# tact-switches2.net
KiCad netlist of a schematic drawn in EAGLE
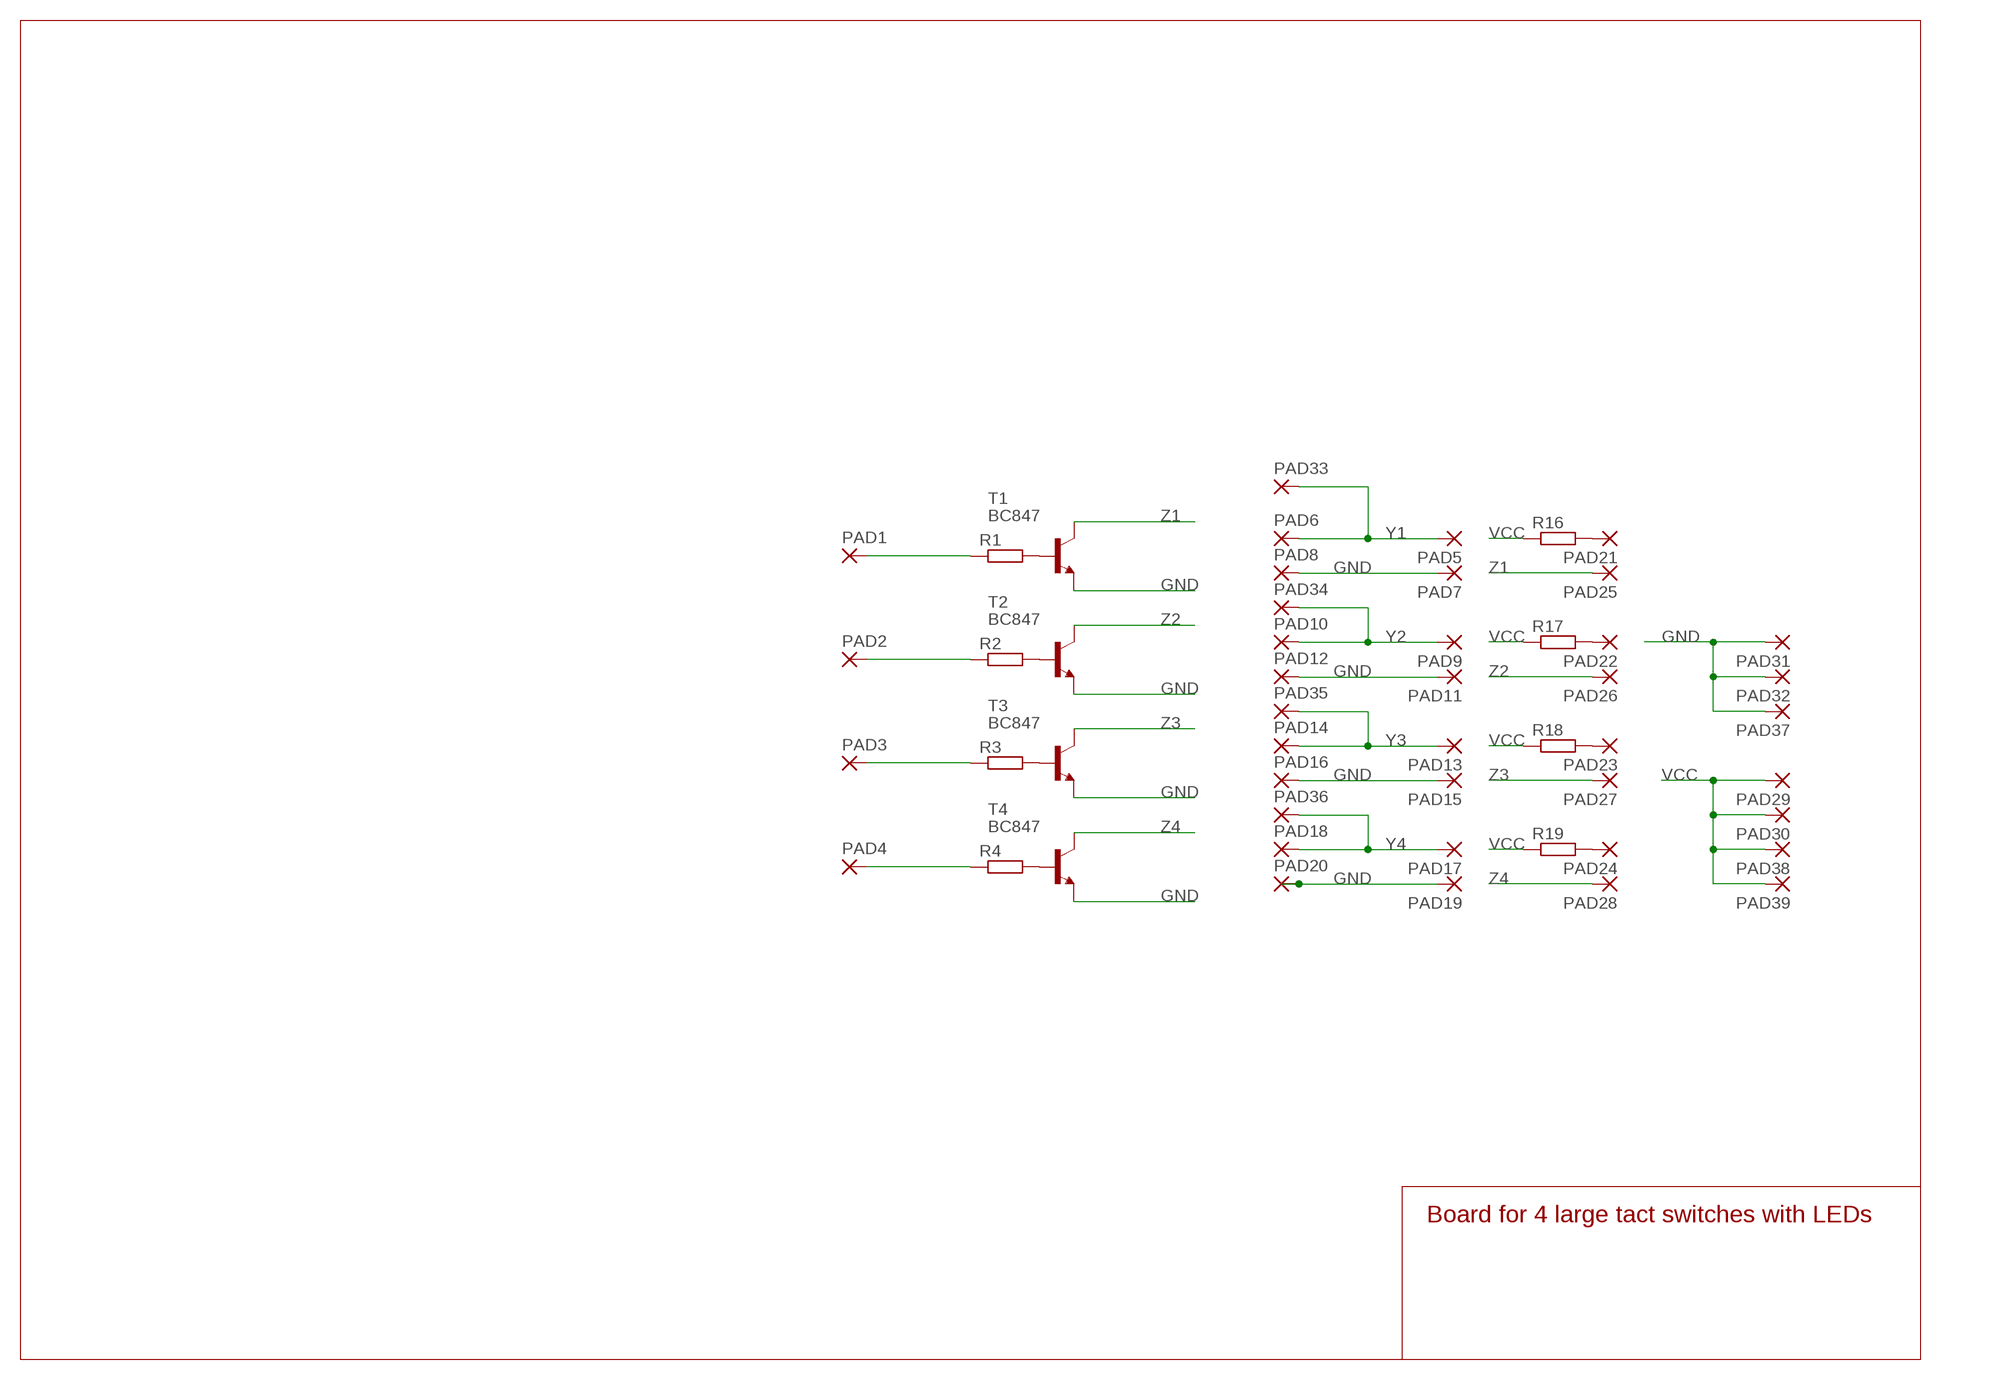
[diagram p0: schematic, sheet 1]

(export (version "E")
  (design (tool "Eeschema 10.0.6"))
  (components
    (comp (ref "PAD1")
      (value "1,6/0,8")
      (footprint "eagle-import:1,6_0,8")
      (libsource (lib "eagle-import") (part "1,6/0,8"))
    )
    (comp (ref "PAD2")
      (value "1,6/0,8")
      (footprint "eagle-import:1,6_0,8")
      (libsource (lib "eagle-import") (part "1,6/0,8"))
    )
    (comp (ref "PAD3")
      (value "1,6/0,8")
      (footprint "eagle-import:1,6_0,8")
      (libsource (lib "eagle-import") (part "1,6/0,8"))
    )
    (comp (ref "PAD4")
      (value "1,6/0,8")
      (footprint "eagle-import:1,6_0,8")
      (libsource (lib "eagle-import") (part "1,6/0,8"))
    )
    (comp (ref "PAD5")
      (value "1,6/0,8")
      (footprint "eagle-import:1,6_0,8")
      (libsource (lib "eagle-import") (part "1,6/0,8"))
    )
    (comp (ref "PAD6")
      (value "1,6/0,8")
      (footprint "eagle-import:1,6_0,8")
      (libsource (lib "eagle-import") (part "1,6/0,8"))
    )
    (comp (ref "PAD7")
      (value "1,6/0,8")
      (footprint "eagle-import:1,6_0,8")
      (libsource (lib "eagle-import") (part "1,6/0,8"))
    )
    (comp (ref "PAD8")
      (value "1,6/0,8")
      (footprint "eagle-import:1,6_0,8")
      (libsource (lib "eagle-import") (part "1,6/0,8"))
    )
    (comp (ref "PAD9")
      (value "1,6/0,8")
      (footprint "eagle-import:1,6_0,8")
      (libsource (lib "eagle-import") (part "1,6/0,8"))
    )
    (comp (ref "PAD10")
      (value "1,6/0,8")
      (footprint "eagle-import:1,6_0,8")
      (libsource (lib "eagle-import") (part "1,6/0,8"))
    )
    (comp (ref "PAD11")
      (value "1,6/0,8")
      (footprint "eagle-import:1,6_0,8")
      (libsource (lib "eagle-import") (part "1,6/0,8"))
    )
    (comp (ref "PAD12")
      (value "1,6/0,8")
      (footprint "eagle-import:1,6_0,8")
      (libsource (lib "eagle-import") (part "1,6/0,8"))
    )
    (comp (ref "PAD13")
      (value "1,6/0,8")
      (footprint "eagle-import:1,6_0,8")
      (libsource (lib "eagle-import") (part "1,6/0,8"))
    )
    (comp (ref "PAD14")
      (value "1,6/0,8")
      (footprint "eagle-import:1,6_0,8")
      (libsource (lib "eagle-import") (part "1,6/0,8"))
    )
    (comp (ref "PAD15")
      (value "1,6/0,8")
      (footprint "eagle-import:1,6_0,8")
      (libsource (lib "eagle-import") (part "1,6/0,8"))
    )
    (comp (ref "PAD16")
      (value "1,6/0,8")
      (footprint "eagle-import:1,6_0,8")
      (libsource (lib "eagle-import") (part "1,6/0,8"))
    )
    (comp (ref "PAD17")
      (value "1,6/0,8")
      (footprint "eagle-import:1,6_0,8")
      (libsource (lib "eagle-import") (part "1,6/0,8"))
    )
    (comp (ref "PAD18")
      (value "1,6/0,8")
      (footprint "eagle-import:1,6_0,8")
      (libsource (lib "eagle-import") (part "1,6/0,8"))
    )
    (comp (ref "PAD19")
      (value "1,6/0,8")
      (footprint "eagle-import:1,6_0,8")
      (libsource (lib "eagle-import") (part "1,6/0,8"))
    )
    (comp (ref "PAD20")
      (value "1,6/0,8")
      (footprint "eagle-import:1,6_0,8")
      (libsource (lib "eagle-import") (part "1,6/0,8"))
    )
    (comp (ref "PAD21")
      (value "1,6/0,8")
      (footprint "eagle-import:1,6_0,8")
      (libsource (lib "eagle-import") (part "1,6/0,8"))
    )
    (comp (ref "PAD22")
      (value "1,6/0,8")
      (footprint "eagle-import:1,6_0,8")
      (libsource (lib "eagle-import") (part "1,6/0,8"))
    )
    (comp (ref "PAD23")
      (value "1,6/0,8")
      (footprint "eagle-import:1,6_0,8")
      (libsource (lib "eagle-import") (part "1,6/0,8"))
    )
    (comp (ref "PAD24")
      (value "1,6/0,8")
      (footprint "eagle-import:1,6_0,8")
      (libsource (lib "eagle-import") (part "1,6/0,8"))
    )
    (comp (ref "PAD25")
      (value "1,6/0,8")
      (footprint "eagle-import:1,6_0,8")
      (libsource (lib "eagle-import") (part "1,6/0,8"))
    )
    (comp (ref "PAD26")
      (value "1,6/0,8")
      (footprint "eagle-import:1,6_0,8")
      (libsource (lib "eagle-import") (part "1,6/0,8"))
    )
    (comp (ref "PAD27")
      (value "1,6/0,8")
      (footprint "eagle-import:1,6_0,8")
      (libsource (lib "eagle-import") (part "1,6/0,8"))
    )
    (comp (ref "PAD28")
      (value "1,6/0,8")
      (footprint "eagle-import:1,6_0,8")
      (libsource (lib "eagle-import") (part "1,6/0,8"))
    )
    (comp (ref "PAD29")
      (value "1,6/0,8")
      (footprint "eagle-import:1,6_0,8")
      (libsource (lib "eagle-import") (part "1,6/0,8"))
    )
    (comp (ref "PAD30")
      (value "1,6/0,8")
      (footprint "eagle-import:1,6_0,8")
      (libsource (lib "eagle-import") (part "1,6/0,8"))
    )
    (comp (ref "PAD31")
      (value "1,6/0,8")
      (footprint "eagle-import:1,6_0,8")
      (libsource (lib "eagle-import") (part "1,6/0,8"))
    )
    (comp (ref "PAD32")
      (value "1,6/0,8")
      (footprint "eagle-import:1,6_0,8")
      (libsource (lib "eagle-import") (part "1,6/0,8"))
    )
    (comp (ref "PAD33")
      (value "1,6/0,8")
      (footprint "eagle-import:1,6_0,8")
      (libsource (lib "eagle-import") (part "1,6/0,8"))
    )
    (comp (ref "PAD34")
      (value "1,6/0,8")
      (footprint "eagle-import:1,6_0,8")
      (libsource (lib "eagle-import") (part "1,6/0,8"))
    )
    (comp (ref "PAD35")
      (value "1,6/0,8")
      (footprint "eagle-import:1,6_0,8")
      (libsource (lib "eagle-import") (part "1,6/0,8"))
    )
    (comp (ref "PAD36")
      (value "1,6/0,8")
      (footprint "eagle-import:1,6_0,8")
      (libsource (lib "eagle-import") (part "1,6/0,8"))
    )
    (comp (ref "PAD37")
      (value "1,6/0,8")
      (footprint "eagle-import:1,6_0,8")
      (libsource (lib "eagle-import") (part "1,6/0,8"))
    )
    (comp (ref "PAD38")
      (value "1,6/0,8")
      (footprint "eagle-import:1,6_0,8")
      (libsource (lib "eagle-import") (part "1,6/0,8"))
    )
    (comp (ref "PAD39")
      (value "1,6/0,8")
      (footprint "eagle-import:1,6_0,8")
      (libsource (lib "eagle-import") (part "1,6/0,8"))
    )
    (comp (ref "R1")
      (value "R-EU_M0805")
      (footprint "eagle-import:M0805")
      (libsource (lib "eagle-import") (part "R-EU_M0805"))
    )
    (comp (ref "R2")
      (value "R-EU_M0805")
      (footprint "eagle-import:M0805")
      (libsource (lib "eagle-import") (part "R-EU_M0805"))
    )
    (comp (ref "R3")
      (value "R-EU_M0805")
      (footprint "eagle-import:M0805")
      (libsource (lib "eagle-import") (part "R-EU_M0805"))
    )
    (comp (ref "R4")
      (value "R-EU_M0805")
      (footprint "eagle-import:M0805")
      (libsource (lib "eagle-import") (part "R-EU_M0805"))
    )
    (comp (ref "R16")
      (value "R-EU_M0805")
      (footprint "eagle-import:M0805")
      (libsource (lib "eagle-import") (part "R-EU_M0805"))
    )
    (comp (ref "R17")
      (value "R-EU_M0805")
      (footprint "eagle-import:M0805")
      (libsource (lib "eagle-import") (part "R-EU_M0805"))
    )
    (comp (ref "R18")
      (value "R-EU_M0805")
      (footprint "eagle-import:M0805")
      (libsource (lib "eagle-import") (part "R-EU_M0805"))
    )
    (comp (ref "R19")
      (value "R-EU_M0805")
      (footprint "eagle-import:M0805")
      (libsource (lib "eagle-import") (part "R-EU_M0805"))
    )
    (comp (ref "T1")
      (value "BC847")
      (footprint "eagle-import:SOT23")
      (libsource (lib "eagle-import") (part "BC847"))
    )
    (comp (ref "T2")
      (value "BC847")
      (footprint "eagle-import:SOT23")
      (libsource (lib "eagle-import") (part "BC847"))
    )
    (comp (ref "T3")
      (value "BC847")
      (footprint "eagle-import:SOT23")
      (libsource (lib "eagle-import") (part "BC847"))
    )
    (comp (ref "T4")
      (value "BC847")
      (footprint "eagle-import:SOT23")
      (libsource (lib "eagle-import") (part "BC847"))
    )
  )
  (nets
    (net (code "1") (name "/GND") (class "Default")
      (node (ref "PAD11") (pin "1") (pinfunction "P_1") (pintype "passive"))
      (node (ref "PAD12") (pin "1") (pinfunction "P_1") (pintype "passive"))
      (node (ref "PAD15") (pin "1") (pinfunction "P_1") (pintype "passive"))
      (node (ref "PAD16") (pin "1") (pinfunction "P_1") (pintype "passive"))
      (node (ref "PAD19") (pin "1") (pinfunction "P_1") (pintype "passive"))
      (node (ref "PAD20") (pin "1") (pinfunction "P_1") (pintype "passive"))
      (node (ref "PAD31") (pin "1") (pinfunction "P_1") (pintype "passive"))
      (node (ref "PAD32") (pin "1") (pinfunction "P_1") (pintype "passive"))
      (node (ref "PAD37") (pin "1") (pinfunction "P_1") (pintype "passive"))
      (node (ref "PAD7") (pin "1") (pinfunction "P_1") (pintype "passive"))
      (node (ref "PAD8") (pin "1") (pinfunction "P_1") (pintype "passive"))
      (node (ref "T1") (pin "2") (pinfunction "E_2") (pintype "passive"))
      (node (ref "T2") (pin "2") (pinfunction "E_2") (pintype "passive"))
      (node (ref "T3") (pin "2") (pinfunction "E_2") (pintype "passive"))
      (node (ref "T4") (pin "2") (pinfunction "E_2") (pintype "passive"))
    )
    (net (code "2") (name "/VCC") (class "Default")
      (node (ref "PAD29") (pin "1") (pinfunction "P_1") (pintype "passive"))
      (node (ref "PAD30") (pin "1") (pinfunction "P_1") (pintype "passive"))
      (node (ref "PAD38") (pin "1") (pinfunction "P_1") (pintype "passive"))
      (node (ref "PAD39") (pin "1") (pinfunction "P_1") (pintype "passive"))
      (node (ref "R16") (pin "1") (pinfunction "1_1") (pintype "passive"))
      (node (ref "R17") (pin "1") (pinfunction "1_1") (pintype "passive"))
      (node (ref "R18") (pin "1") (pinfunction "1_1") (pintype "passive"))
      (node (ref "R19") (pin "1") (pinfunction "1_1") (pintype "passive"))
    )
    (net (code "3") (name "/Y1") (class "Default")
      (node (ref "PAD33") (pin "1") (pinfunction "P_1") (pintype "passive"))
      (node (ref "PAD5") (pin "1") (pinfunction "P_1") (pintype "passive"))
      (node (ref "PAD6") (pin "1") (pinfunction "P_1") (pintype "passive"))
    )
    (net (code "4") (name "/Y2") (class "Default")
      (node (ref "PAD10") (pin "1") (pinfunction "P_1") (pintype "passive"))
      (node (ref "PAD34") (pin "1") (pinfunction "P_1") (pintype "passive"))
      (node (ref "PAD9") (pin "1") (pinfunction "P_1") (pintype "passive"))
    )
    (net (code "5") (name "/Y3") (class "Default")
      (node (ref "PAD13") (pin "1") (pinfunction "P_1") (pintype "passive"))
      (node (ref "PAD14") (pin "1") (pinfunction "P_1") (pintype "passive"))
      (node (ref "PAD35") (pin "1") (pinfunction "P_1") (pintype "passive"))
    )
    (net (code "6") (name "/Y4") (class "Default")
      (node (ref "PAD17") (pin "1") (pinfunction "P_1") (pintype "passive"))
      (node (ref "PAD18") (pin "1") (pinfunction "P_1") (pintype "passive"))
      (node (ref "PAD36") (pin "1") (pinfunction "P_1") (pintype "passive"))
    )
    (net (code "7") (name "/Z1") (class "Default")
      (node (ref "PAD25") (pin "1") (pinfunction "P_1") (pintype "passive"))
      (node (ref "T1") (pin "3") (pinfunction "C_3") (pintype "passive"))
    )
    (net (code "8") (name "/Z2") (class "Default")
      (node (ref "PAD26") (pin "1") (pinfunction "P_1") (pintype "passive"))
      (node (ref "T2") (pin "3") (pinfunction "C_3") (pintype "passive"))
    )
    (net (code "9") (name "/Z3") (class "Default")
      (node (ref "PAD27") (pin "1") (pinfunction "P_1") (pintype "passive"))
      (node (ref "T3") (pin "3") (pinfunction "C_3") (pintype "passive"))
    )
    (net (code "10") (name "/Z4") (class "Default")
      (node (ref "PAD28") (pin "1") (pinfunction "P_1") (pintype "passive"))
      (node (ref "T4") (pin "3") (pinfunction "C_3") (pintype "passive"))
    )
    (net (code "11") (name "Net-(PAD1-P)") (class "Default")
      (node (ref "PAD1") (pin "1") (pinfunction "P_1") (pintype "passive"))
      (node (ref "R1") (pin "1") (pinfunction "1_1") (pintype "passive"))
    )
    (net (code "12") (name "Net-(PAD2-P)") (class "Default")
      (node (ref "PAD2") (pin "1") (pinfunction "P_1") (pintype "passive"))
      (node (ref "R2") (pin "1") (pinfunction "1_1") (pintype "passive"))
    )
    (net (code "13") (name "Net-(PAD3-P)") (class "Default")
      (node (ref "PAD3") (pin "1") (pinfunction "P_1") (pintype "passive"))
      (node (ref "R3") (pin "1") (pinfunction "1_1") (pintype "passive"))
    )
    (net (code "14") (name "Net-(PAD4-P)") (class "Default")
      (node (ref "PAD4") (pin "1") (pinfunction "P_1") (pintype "passive"))
      (node (ref "R4") (pin "1") (pinfunction "1_1") (pintype "passive"))
    )
    (net (code "15") (name "Net-(PAD21-P)") (class "Default")
      (node (ref "PAD21") (pin "1") (pinfunction "P_1") (pintype "passive"))
      (node (ref "R16") (pin "2") (pinfunction "2_2") (pintype "passive"))
    )
    (net (code "16") (name "Net-(PAD22-P)") (class "Default")
      (node (ref "PAD22") (pin "1") (pinfunction "P_1") (pintype "passive"))
      (node (ref "R17") (pin "2") (pinfunction "2_2") (pintype "passive"))
    )
    (net (code "17") (name "Net-(PAD23-P)") (class "Default")
      (node (ref "PAD23") (pin "1") (pinfunction "P_1") (pintype "passive"))
      (node (ref "R18") (pin "2") (pinfunction "2_2") (pintype "passive"))
    )
    (net (code "18") (name "Net-(PAD24-P)") (class "Default")
      (node (ref "PAD24") (pin "1") (pinfunction "P_1") (pintype "passive"))
      (node (ref "R19") (pin "2") (pinfunction "2_2") (pintype "passive"))
    )
    (net (code "19") (name "Net-(T1-B)") (class "Default")
      (node (ref "R1") (pin "2") (pinfunction "2_2") (pintype "passive"))
      (node (ref "T1") (pin "1") (pinfunction "B_1") (pintype "passive"))
    )
    (net (code "20") (name "Net-(T2-B)") (class "Default")
      (node (ref "R2") (pin "2") (pinfunction "2_2") (pintype "passive"))
      (node (ref "T2") (pin "1") (pinfunction "B_1") (pintype "passive"))
    )
    (net (code "21") (name "Net-(T3-B)") (class "Default")
      (node (ref "R3") (pin "2") (pinfunction "2_2") (pintype "passive"))
      (node (ref "T3") (pin "1") (pinfunction "B_1") (pintype "passive"))
    )
    (net (code "22") (name "Net-(T4-B)") (class "Default")
      (node (ref "R4") (pin "2") (pinfunction "2_2") (pintype "passive"))
      (node (ref "T4") (pin "1") (pinfunction "B_1") (pintype "passive"))
    )
  )
)
